# test.net
KiCad netlist of a schematic drawn in EAGLE
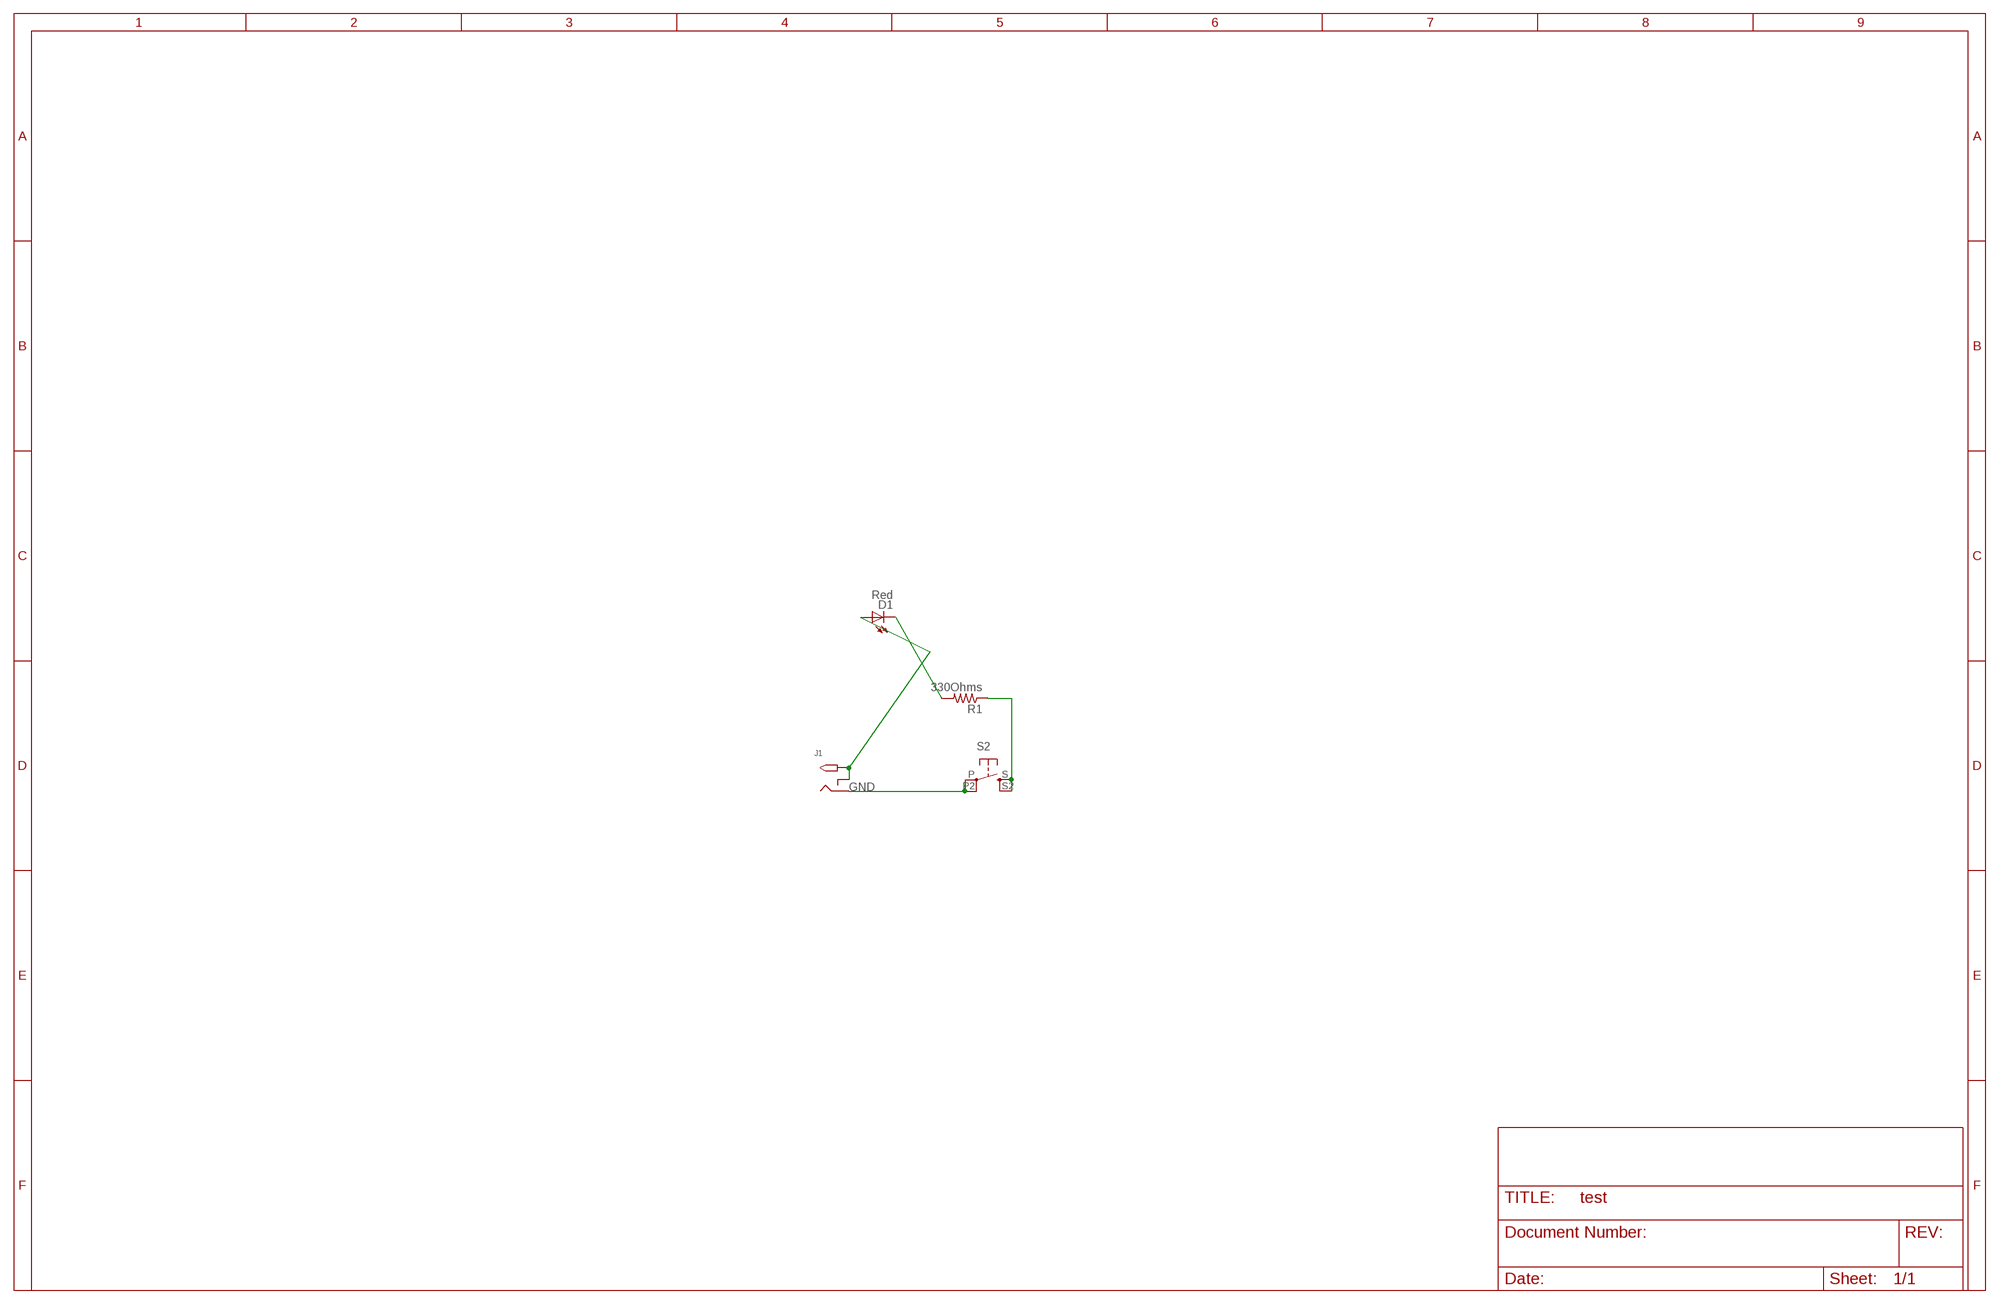
[diagram p0: schematic, sheet 1]

(export (version "E")
  (design (tool "Eeschema 10.0.6"))
  (components
    (comp (ref "D1")
      (value "Red")
      (footprint "eagle-import:LED5MM")
      (fields (field (name "CREATOR") "Swanson") (field (name "REVIEWER") "Swanson"))
      (libsource (lib "eagle-import") (part "LED5MM"))
    )
    (comp (ref "J1")
      (value "2.1MMJACKTHM")
      (footprint "eagle-import:PJ-102A")
      (fields (field (name "CREATOR") "Swanson") (field (name "REVIEWER") "Swanson"))
      (libsource (lib "eagle-import") (part "2.1MMJACKTHM"))
    )
    (comp (ref "R1")
      (value "330Ohms")
      (footprint "eagle-import:RESAD1160W55L680D260_HS")
      (fields (field (name "CREATOR") "Swanson") (field (name "REVIEWER") "Swanson"))
      (libsource (lib "eagle-import") (part "RESISTORTH-1/4W-CARBON"))
    )
    (comp (ref "S2")
      (value "PUSH-BUTTON-SQUARE")
      (footprint "eagle-import:BUTTON-TACTILE-SQUARE-ADAFRUIT1010")
      (fields (field (name "CREATOR") "Swanson") (field (name "REVIEWER") "Swanson"))
      (libsource (lib "eagle-import") (part "PUSH-BUTTON-SQUARE"))
    )
  )
  (nets
    (net (code "1") (name "/GND") (class "Default")
      (node (ref "J1") (pin "RING") (pinfunction "RING_RING") (pintype "bidirectional"))
      (node (ref "S2") (pin "P") (pinfunction "P_P") (pintype "passive"))
      (node (ref "S2") (pin "P2") (pinfunction "P1_P2") (pintype "passive"))
    )
    (net (code "2") (name "Net-(D1-C)") (class "Default")
      (node (ref "D1") (pin "K") (pinfunction "C_K") (pintype "passive"))
      (node (ref "R1") (pin "2") (pinfunction "2_2") (pintype "passive"))
    )
    (net (code "3") (name "Net-(D1-PadA)") (class "Default")
      (node (ref "D1") (pin "A") (pinfunction "A_A") (pintype "passive"))
      (node (ref "J1") (pin "RING_SW") (pinfunction "RING_SW_RING_SW") (pintype "bidirectional"))
      (node (ref "J1") (pin "TIP") (pinfunction "TIP_TIP") (pintype "bidirectional"))
    )
    (net (code "4") (name "Net-(S2-S1)") (class "Default")
      (node (ref "R1") (pin "1") (pinfunction "1_1") (pintype "passive"))
      (node (ref "S2") (pin "S") (pinfunction "S_S") (pintype "passive"))
      (node (ref "S2") (pin "S2") (pinfunction "S1_S2") (pintype "passive"))
    )
  )
)
